# GasSensor.net
KiCad netlist of a schematic drawn in Altium Designer
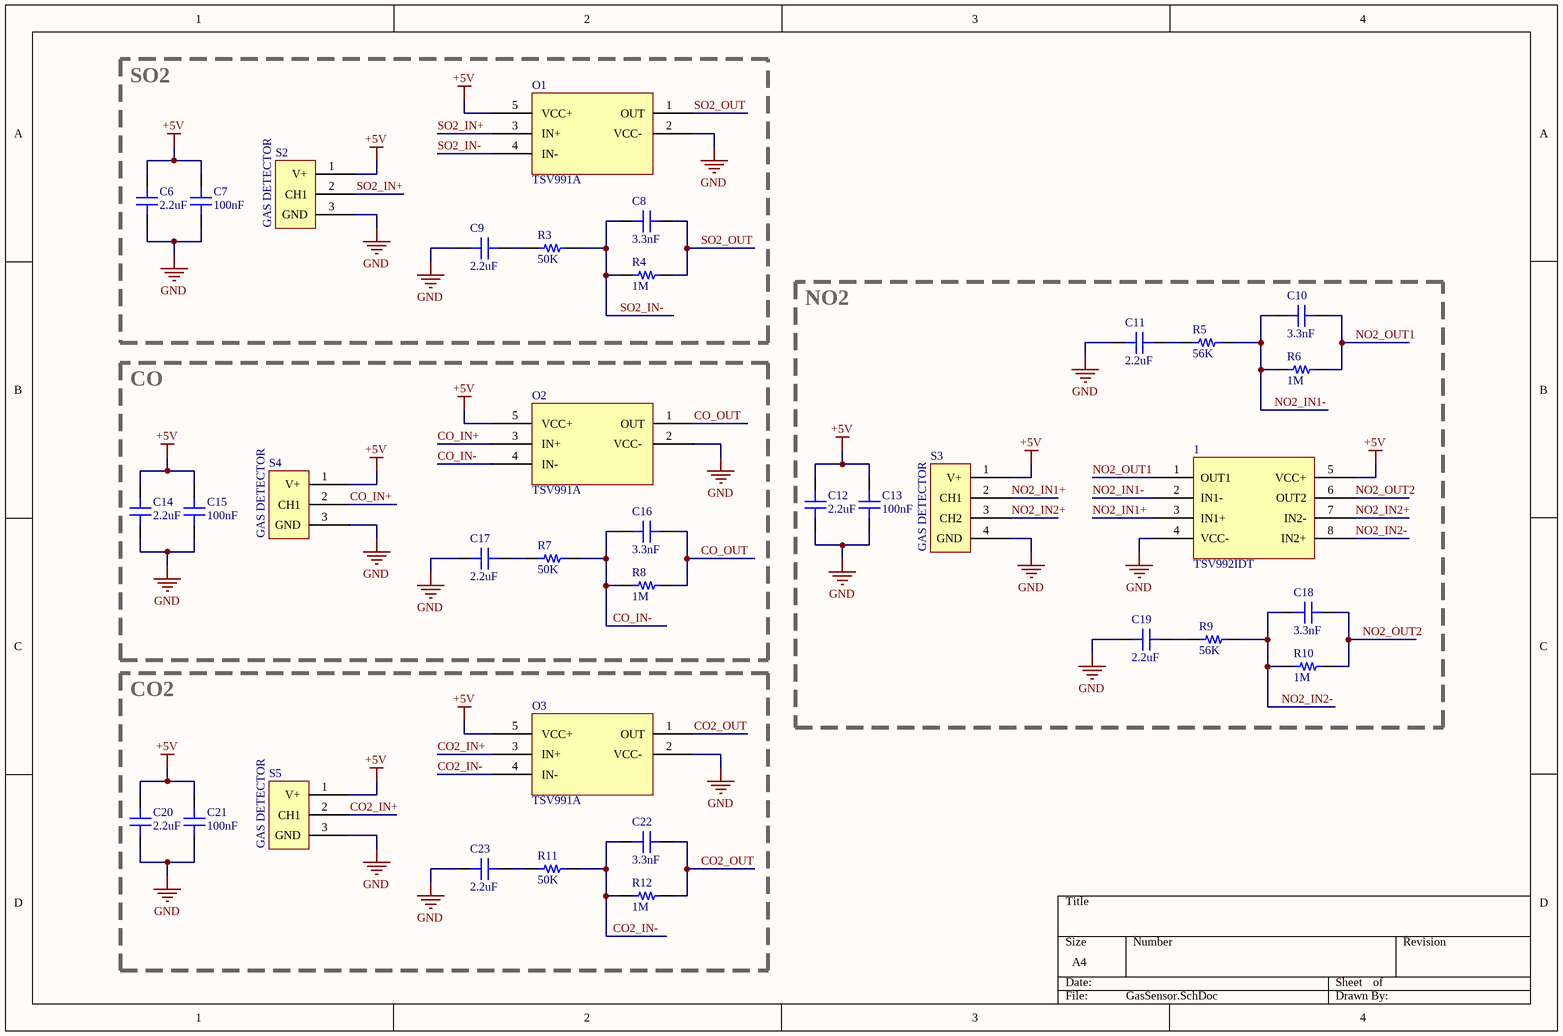
[diagram p0: GasSensor.SchDoc]

(export (version "E")
  (design (tool "Eeschema 10.0.6"))
  (components
    (comp (ref "1")
      (value "TSV992IDT")
      (footprint "SOIC8")
      (description "Operational Amplifiers Op Amps SOIC-8 2 Channel 20 MHz")
      (libsource (lib "hava_kalitesi_olcumu") (part "TSV992IDT"))
    )
    (comp (ref "C6")
      (value "2.2uF")
      (footprint "CAP 0603_1608")
      (description "CERAMİC 1206 SMD")
      (libsource (lib "hava_kalitesi_olcumu") (part "2.2uF"))
    )
    (comp (ref "C7")
      (value "100nF")
      (footprint "CAP 0603_1608")
      (description "CERAMİC 1206 SMD")
      (libsource (lib "hava_kalitesi_olcumu") (part "100nF"))
    )
    (comp (ref "C8")
      (value "3.3nF")
      (footprint "CAP 0603_1608")
      (description "CERAMİC 1206 SMD")
      (libsource (lib "hava_kalitesi_olcumu") (part "3.3nF"))
    )
    (comp (ref "C9")
      (value "2.2uF")
      (footprint "CAP 0603_1608")
      (description "CERAMİC 1206 SMD")
      (libsource (lib "hava_kalitesi_olcumu") (part "2.2uF"))
    )
    (comp (ref "C10")
      (value "3.3nF")
      (footprint "CAP 0603_1608")
      (description "CERAMİC 1206 SMD")
      (libsource (lib "hava_kalitesi_olcumu") (part "3.3nF"))
    )
    (comp (ref "C11")
      (value "2.2uF")
      (footprint "CAP 0603_1608")
      (description "CERAMİC 1206 SMD")
      (libsource (lib "hava_kalitesi_olcumu") (part "2.2uF"))
    )
    (comp (ref "C12")
      (value "2.2uF")
      (footprint "CAP 0603_1608")
      (description "CERAMİC 1206 SMD")
      (libsource (lib "hava_kalitesi_olcumu") (part "2.2uF"))
    )
    (comp (ref "C13")
      (value "100nF")
      (footprint "CAP 0603_1608")
      (description "CERAMİC 1206 SMD")
      (libsource (lib "hava_kalitesi_olcumu") (part "100nF"))
    )
    (comp (ref "C14")
      (value "2.2uF")
      (footprint "CAP 0603_1608")
      (description "CERAMİC 1206 SMD")
      (libsource (lib "hava_kalitesi_olcumu") (part "2.2uF"))
    )
    (comp (ref "C15")
      (value "100nF")
      (footprint "CAP 0603_1608")
      (description "CERAMİC 1206 SMD")
      (libsource (lib "hava_kalitesi_olcumu") (part "100nF"))
    )
    (comp (ref "C16")
      (value "3.3nF")
      (footprint "CAP 0603_1608")
      (description "CERAMİC 1206 SMD")
      (libsource (lib "hava_kalitesi_olcumu") (part "3.3nF"))
    )
    (comp (ref "C17")
      (value "2.2uF")
      (footprint "CAP 0603_1608")
      (description "CERAMİC 1206 SMD")
      (libsource (lib "hava_kalitesi_olcumu") (part "2.2uF"))
    )
    (comp (ref "C18")
      (value "3.3nF")
      (footprint "CAP 0603_1608")
      (description "CERAMİC 1206 SMD")
      (libsource (lib "hava_kalitesi_olcumu") (part "3.3nF"))
    )
    (comp (ref "C19")
      (value "2.2uF")
      (footprint "CAP 0603_1608")
      (description "CERAMİC 1206 SMD")
      (libsource (lib "hava_kalitesi_olcumu") (part "2.2uF"))
    )
    (comp (ref "C20")
      (value "2.2uF")
      (footprint "CAP 0603_1608")
      (description "CERAMİC 1206 SMD")
      (libsource (lib "hava_kalitesi_olcumu") (part "2.2uF"))
    )
    (comp (ref "C21")
      (value "100nF")
      (footprint "CAP 0603_1608")
      (description "CERAMİC 1206 SMD")
      (libsource (lib "hava_kalitesi_olcumu") (part "100nF"))
    )
    (comp (ref "C22")
      (value "3.3nF")
      (footprint "CAP 0603_1608")
      (description "CERAMİC 1206 SMD")
      (libsource (lib "hava_kalitesi_olcumu") (part "3.3nF"))
    )
    (comp (ref "C23")
      (value "2.2uF")
      (footprint "CAP 0603_1608")
      (description "CERAMİC 1206 SMD")
      (libsource (lib "hava_kalitesi_olcumu") (part "2.2uF"))
    )
    (comp (ref "O1")
      (value "TSV991A")
      (footprint "SOT23-5")
      (description "Operational Amplifiers Op Amps SOT23-5 1 Channel 20 MHz")
      (libsource (lib "hava_kalitesi_olcumu") (part "TSV991A"))
    )
    (comp (ref "O2")
      (value "TSV991A")
      (footprint "SOT23-5")
      (description "Operational Amplifiers Op Amps SOT23-5 1 Channel 20 MHz")
      (libsource (lib "hava_kalitesi_olcumu") (part "TSV991A"))
    )
    (comp (ref "O3")
      (value "TSV991A")
      (footprint "SOT23-5")
      (description "Operational Amplifiers Op Amps SOT23-5 1 Channel 20 MHz")
      (libsource (lib "hava_kalitesi_olcumu") (part "TSV991A"))
    )
    (comp (ref "R3")
      (value "50K")
      (footprint "RES 0603_1608")
      (description "SMT RES 1206")
      (libsource (lib "hava_kalitesi_olcumu") (part "50K"))
    )
    (comp (ref "R4")
      (value "1M")
      (footprint "RES 0603_1608")
      (description "SMT RES 1206")
      (libsource (lib "hava_kalitesi_olcumu") (part "1M"))
    )
    (comp (ref "R5")
      (value "56K")
      (footprint "RES 0603_1608")
      (description "SMT RES 1206")
      (libsource (lib "hava_kalitesi_olcumu") (part "56K"))
    )
    (comp (ref "R6")
      (value "1M")
      (footprint "RES 0603_1608")
      (description "SMT RES 1206")
      (libsource (lib "hava_kalitesi_olcumu") (part "1M"))
    )
    (comp (ref "R7")
      (value "50K")
      (footprint "RES 0603_1608")
      (description "SMT RES 1206")
      (libsource (lib "hava_kalitesi_olcumu") (part "50K"))
    )
    (comp (ref "R8")
      (value "1M")
      (footprint "RES 0603_1608")
      (description "SMT RES 1206")
      (libsource (lib "hava_kalitesi_olcumu") (part "1M"))
    )
    (comp (ref "R9")
      (value "56K")
      (footprint "RES 0603_1608")
      (description "SMT RES 1206")
      (libsource (lib "hava_kalitesi_olcumu") (part "56K"))
    )
    (comp (ref "R10")
      (value "1M")
      (footprint "RES 0603_1608")
      (description "SMT RES 1206")
      (libsource (lib "hava_kalitesi_olcumu") (part "1M"))
    )
    (comp (ref "R11")
      (value "50K")
      (footprint "RES 0603_1608")
      (description "SMT RES 1206")
      (libsource (lib "hava_kalitesi_olcumu") (part "50K"))
    )
    (comp (ref "R12")
      (value "1M")
      (footprint "RES 0603_1608")
      (description "SMT RES 1206")
      (libsource (lib "hava_kalitesi_olcumu") (part "1M"))
    )
    (comp (ref "S2")
      (value "GAS DETECTOR")
      (footprint "TO-39 CIRCLE")
      (description "GAS DETECTOR, ANALOG TO-39, GAS")
      (libsource (lib "hava_kalitesi_olcumu") (part "QGC Circle Sensor"))
    )
    (comp (ref "S3")
      (value "GAS DETECTOR")
      (footprint "TO-39 DUAL")
      (description "GAS DETECTOR, ANALOG TO-39, GAS")
      (libsource (lib "hava_kalitesi_olcumu") (part "QGC Dual Sensor"))
    )
    (comp (ref "S4")
      (value "GAS DETECTOR")
      (footprint "TO-39 CIRCLE")
      (description "GAS DETECTOR, ANALOG TO-39, GAS")
      (libsource (lib "hava_kalitesi_olcumu") (part "QGC Circle Sensor"))
    )
    (comp (ref "S5")
      (value "GAS DETECTOR")
      (footprint "TO-39 CIRCLE")
      (description "GAS DETECTOR, ANALOG TO-39, GAS")
      (libsource (lib "hava_kalitesi_olcumu") (part "QGC Circle Sensor"))
    )
  )
  (nets
    (net (code "1") (name "+5V") (class "Default")
      (node (ref "1") (pin "5") (pinfunction "VCC+_5") (pintype "passive"))
      (node (ref "C12") (pin "1") (pinfunction "1_1") (pintype "passive"))
      (node (ref "C13") (pin "2") (pinfunction "2_2") (pintype "passive"))
      (node (ref "C14") (pin "1") (pinfunction "1_1") (pintype "passive"))
      (node (ref "C15") (pin "2") (pinfunction "2_2") (pintype "passive"))
      (node (ref "C20") (pin "1") (pinfunction "1_1") (pintype "passive"))
      (node (ref "C21") (pin "2") (pinfunction "2_2") (pintype "passive"))
      (node (ref "C6") (pin "1") (pinfunction "1_1") (pintype "passive"))
      (node (ref "C7") (pin "2") (pinfunction "2_2") (pintype "passive"))
      (node (ref "O1") (pin "5") (pinfunction "VCC+_5") (pintype "passive"))
      (node (ref "O2") (pin "5") (pinfunction "VCC+_5") (pintype "passive"))
      (node (ref "O3") (pin "5") (pinfunction "VCC+_5") (pintype "passive"))
      (node (ref "S2") (pin "1") (pinfunction "V+_1") (pintype "passive"))
      (node (ref "S3") (pin "1") (pinfunction "V+_1") (pintype "passive"))
      (node (ref "S4") (pin "1") (pinfunction "V+_1") (pintype "passive"))
      (node (ref "S5") (pin "1") (pinfunction "V+_1") (pintype "passive"))
    )
    (net (code "2") (name "/CO2_IN+") (class "Default")
      (node (ref "O3") (pin "3") (pinfunction "IN+_3") (pintype "passive"))
      (node (ref "S5") (pin "2") (pinfunction "CH1_2") (pintype "passive"))
    )
    (net (code "3") (name "/CO2_IN-") (class "Default")
      (node (ref "C22") (pin "1") (pinfunction "1_1") (pintype "passive"))
      (node (ref "O3") (pin "4") (pinfunction "IN-_4") (pintype "passive"))
      (node (ref "R11") (pin "2") (pinfunction "2_2") (pintype "passive"))
      (node (ref "R12") (pin "1") (pinfunction "1_1") (pintype "passive"))
    )
    (net (code "4") (name "/CO2_OUT") (class "Default")
      (node (ref "C22") (pin "2") (pinfunction "2_2") (pintype "passive"))
      (node (ref "O3") (pin "1") (pinfunction "OUT_1") (pintype "passive"))
      (node (ref "R12") (pin "2") (pinfunction "2_2") (pintype "passive"))
    )
    (net (code "5") (name "/CO_IN+") (class "Default")
      (node (ref "O2") (pin "3") (pinfunction "IN+_3") (pintype "passive"))
      (node (ref "S4") (pin "2") (pinfunction "CH1_2") (pintype "passive"))
    )
    (net (code "6") (name "/CO_IN-") (class "Default")
      (node (ref "C16") (pin "1") (pinfunction "1_1") (pintype "passive"))
      (node (ref "O2") (pin "4") (pinfunction "IN-_4") (pintype "passive"))
      (node (ref "R7") (pin "2") (pinfunction "2_2") (pintype "passive"))
      (node (ref "R8") (pin "1") (pinfunction "1_1") (pintype "passive"))
    )
    (net (code "7") (name "/CO_OUT") (class "Default")
      (node (ref "C16") (pin "2") (pinfunction "2_2") (pintype "passive"))
      (node (ref "O2") (pin "1") (pinfunction "OUT_1") (pintype "passive"))
      (node (ref "R8") (pin "2") (pinfunction "2_2") (pintype "passive"))
    )
    (net (code "8") (name "/NO2_IN1+") (class "Default")
      (node (ref "1") (pin "3") (pinfunction "IN1+_3") (pintype "passive"))
      (node (ref "S3") (pin "2") (pinfunction "CH1_2") (pintype "passive"))
    )
    (net (code "9") (name "/NO2_IN1-") (class "Default")
      (node (ref "1") (pin "2") (pinfunction "IN1-_2") (pintype "passive"))
      (node (ref "C10") (pin "1") (pinfunction "1_1") (pintype "passive"))
      (node (ref "R5") (pin "2") (pinfunction "2_2") (pintype "passive"))
      (node (ref "R6") (pin "1") (pinfunction "1_1") (pintype "passive"))
    )
    (net (code "10") (name "/NO2_IN2+") (class "Default")
      (node (ref "1") (pin "7") (pinfunction "IN2-_7") (pintype "passive"))
      (node (ref "S3") (pin "3") (pinfunction "CH2_3") (pintype "passive"))
    )
    (net (code "11") (name "/NO2_IN2-") (class "Default")
      (node (ref "1") (pin "8") (pinfunction "IN2+_8") (pintype "passive"))
      (node (ref "C18") (pin "1") (pinfunction "1_1") (pintype "passive"))
      (node (ref "R10") (pin "1") (pinfunction "1_1") (pintype "passive"))
      (node (ref "R9") (pin "2") (pinfunction "2_2") (pintype "passive"))
    )
    (net (code "12") (name "/NO2_OUT1") (class "Default")
      (node (ref "1") (pin "1") (pinfunction "OUT1_1") (pintype "passive"))
      (node (ref "C10") (pin "2") (pinfunction "2_2") (pintype "passive"))
      (node (ref "R6") (pin "2") (pinfunction "2_2") (pintype "passive"))
    )
    (net (code "13") (name "/NO2_OUT2") (class "Default")
      (node (ref "1") (pin "6") (pinfunction "OUT2_6") (pintype "passive"))
      (node (ref "C18") (pin "2") (pinfunction "2_2") (pintype "passive"))
      (node (ref "R10") (pin "2") (pinfunction "2_2") (pintype "passive"))
    )
    (net (code "14") (name "/SO2_IN+") (class "Default")
      (node (ref "O1") (pin "3") (pinfunction "IN+_3") (pintype "passive"))
      (node (ref "S2") (pin "2") (pinfunction "CH1_2") (pintype "passive"))
    )
    (net (code "15") (name "/SO2_IN-") (class "Default")
      (node (ref "C8") (pin "1") (pinfunction "1_1") (pintype "passive"))
      (node (ref "O1") (pin "4") (pinfunction "IN-_4") (pintype "passive"))
      (node (ref "R3") (pin "2") (pinfunction "2_2") (pintype "passive"))
      (node (ref "R4") (pin "1") (pinfunction "1_1") (pintype "passive"))
    )
    (net (code "16") (name "/SO2_OUT") (class "Default")
      (node (ref "C8") (pin "2") (pinfunction "2_2") (pintype "passive"))
      (node (ref "O1") (pin "1") (pinfunction "OUT_1") (pintype "passive"))
      (node (ref "R4") (pin "2") (pinfunction "2_2") (pintype "passive"))
    )
    (net (code "17") (name "GND") (class "Default")
      (node (ref "1") (pin "4") (pinfunction "VCC-_4") (pintype "passive"))
      (node (ref "C11") (pin "1") (pinfunction "1_1") (pintype "passive"))
      (node (ref "C12") (pin "2") (pinfunction "2_2") (pintype "passive"))
      (node (ref "C13") (pin "1") (pinfunction "1_1") (pintype "passive"))
      (node (ref "C14") (pin "2") (pinfunction "2_2") (pintype "passive"))
      (node (ref "C15") (pin "1") (pinfunction "1_1") (pintype "passive"))
      (node (ref "C17") (pin "1") (pinfunction "1_1") (pintype "passive"))
      (node (ref "C19") (pin "1") (pinfunction "1_1") (pintype "passive"))
      (node (ref "C20") (pin "2") (pinfunction "2_2") (pintype "passive"))
      (node (ref "C21") (pin "1") (pinfunction "1_1") (pintype "passive"))
      (node (ref "C23") (pin "1") (pinfunction "1_1") (pintype "passive"))
      (node (ref "C6") (pin "2") (pinfunction "2_2") (pintype "passive"))
      (node (ref "C7") (pin "1") (pinfunction "1_1") (pintype "passive"))
      (node (ref "C9") (pin "1") (pinfunction "1_1") (pintype "passive"))
      (node (ref "O1") (pin "2") (pinfunction "VCC-_2") (pintype "passive"))
      (node (ref "O2") (pin "2") (pinfunction "VCC-_2") (pintype "passive"))
      (node (ref "O3") (pin "2") (pinfunction "VCC-_2") (pintype "passive"))
      (node (ref "S2") (pin "3") (pinfunction "GND_3") (pintype "passive"))
      (node (ref "S3") (pin "4") (pinfunction "GND_4") (pintype "passive"))
      (node (ref "S4") (pin "3") (pinfunction "GND_3") (pintype "passive"))
      (node (ref "S5") (pin "3") (pinfunction "GND_3") (pintype "passive"))
    )
    (net (code "18") (name "Net-(C9-Pad2)") (class "Default")
      (node (ref "C9") (pin "2") (pinfunction "2_2") (pintype "passive"))
      (node (ref "R3") (pin "1") (pinfunction "1_1") (pintype "passive"))
    )
    (net (code "19") (name "Net-(C11-Pad2)") (class "Default")
      (node (ref "C11") (pin "2") (pinfunction "2_2") (pintype "passive"))
      (node (ref "R5") (pin "1") (pinfunction "1_1") (pintype "passive"))
    )
    (net (code "20") (name "Net-(C17-Pad2)") (class "Default")
      (node (ref "C17") (pin "2") (pinfunction "2_2") (pintype "passive"))
      (node (ref "R7") (pin "1") (pinfunction "1_1") (pintype "passive"))
    )
    (net (code "21") (name "Net-(C19-Pad2)") (class "Default")
      (node (ref "C19") (pin "2") (pinfunction "2_2") (pintype "passive"))
      (node (ref "R9") (pin "1") (pinfunction "1_1") (pintype "passive"))
    )
    (net (code "22") (name "Net-(C23-Pad2)") (class "Default")
      (node (ref "C23") (pin "2") (pinfunction "2_2") (pintype "passive"))
      (node (ref "R11") (pin "1") (pinfunction "1_1") (pintype "passive"))
    )
  )
)
